# 1-Schematic_Mailbox_Sensor_eLab.net
KiCad netlist of a schematic drawn in EasyEDA
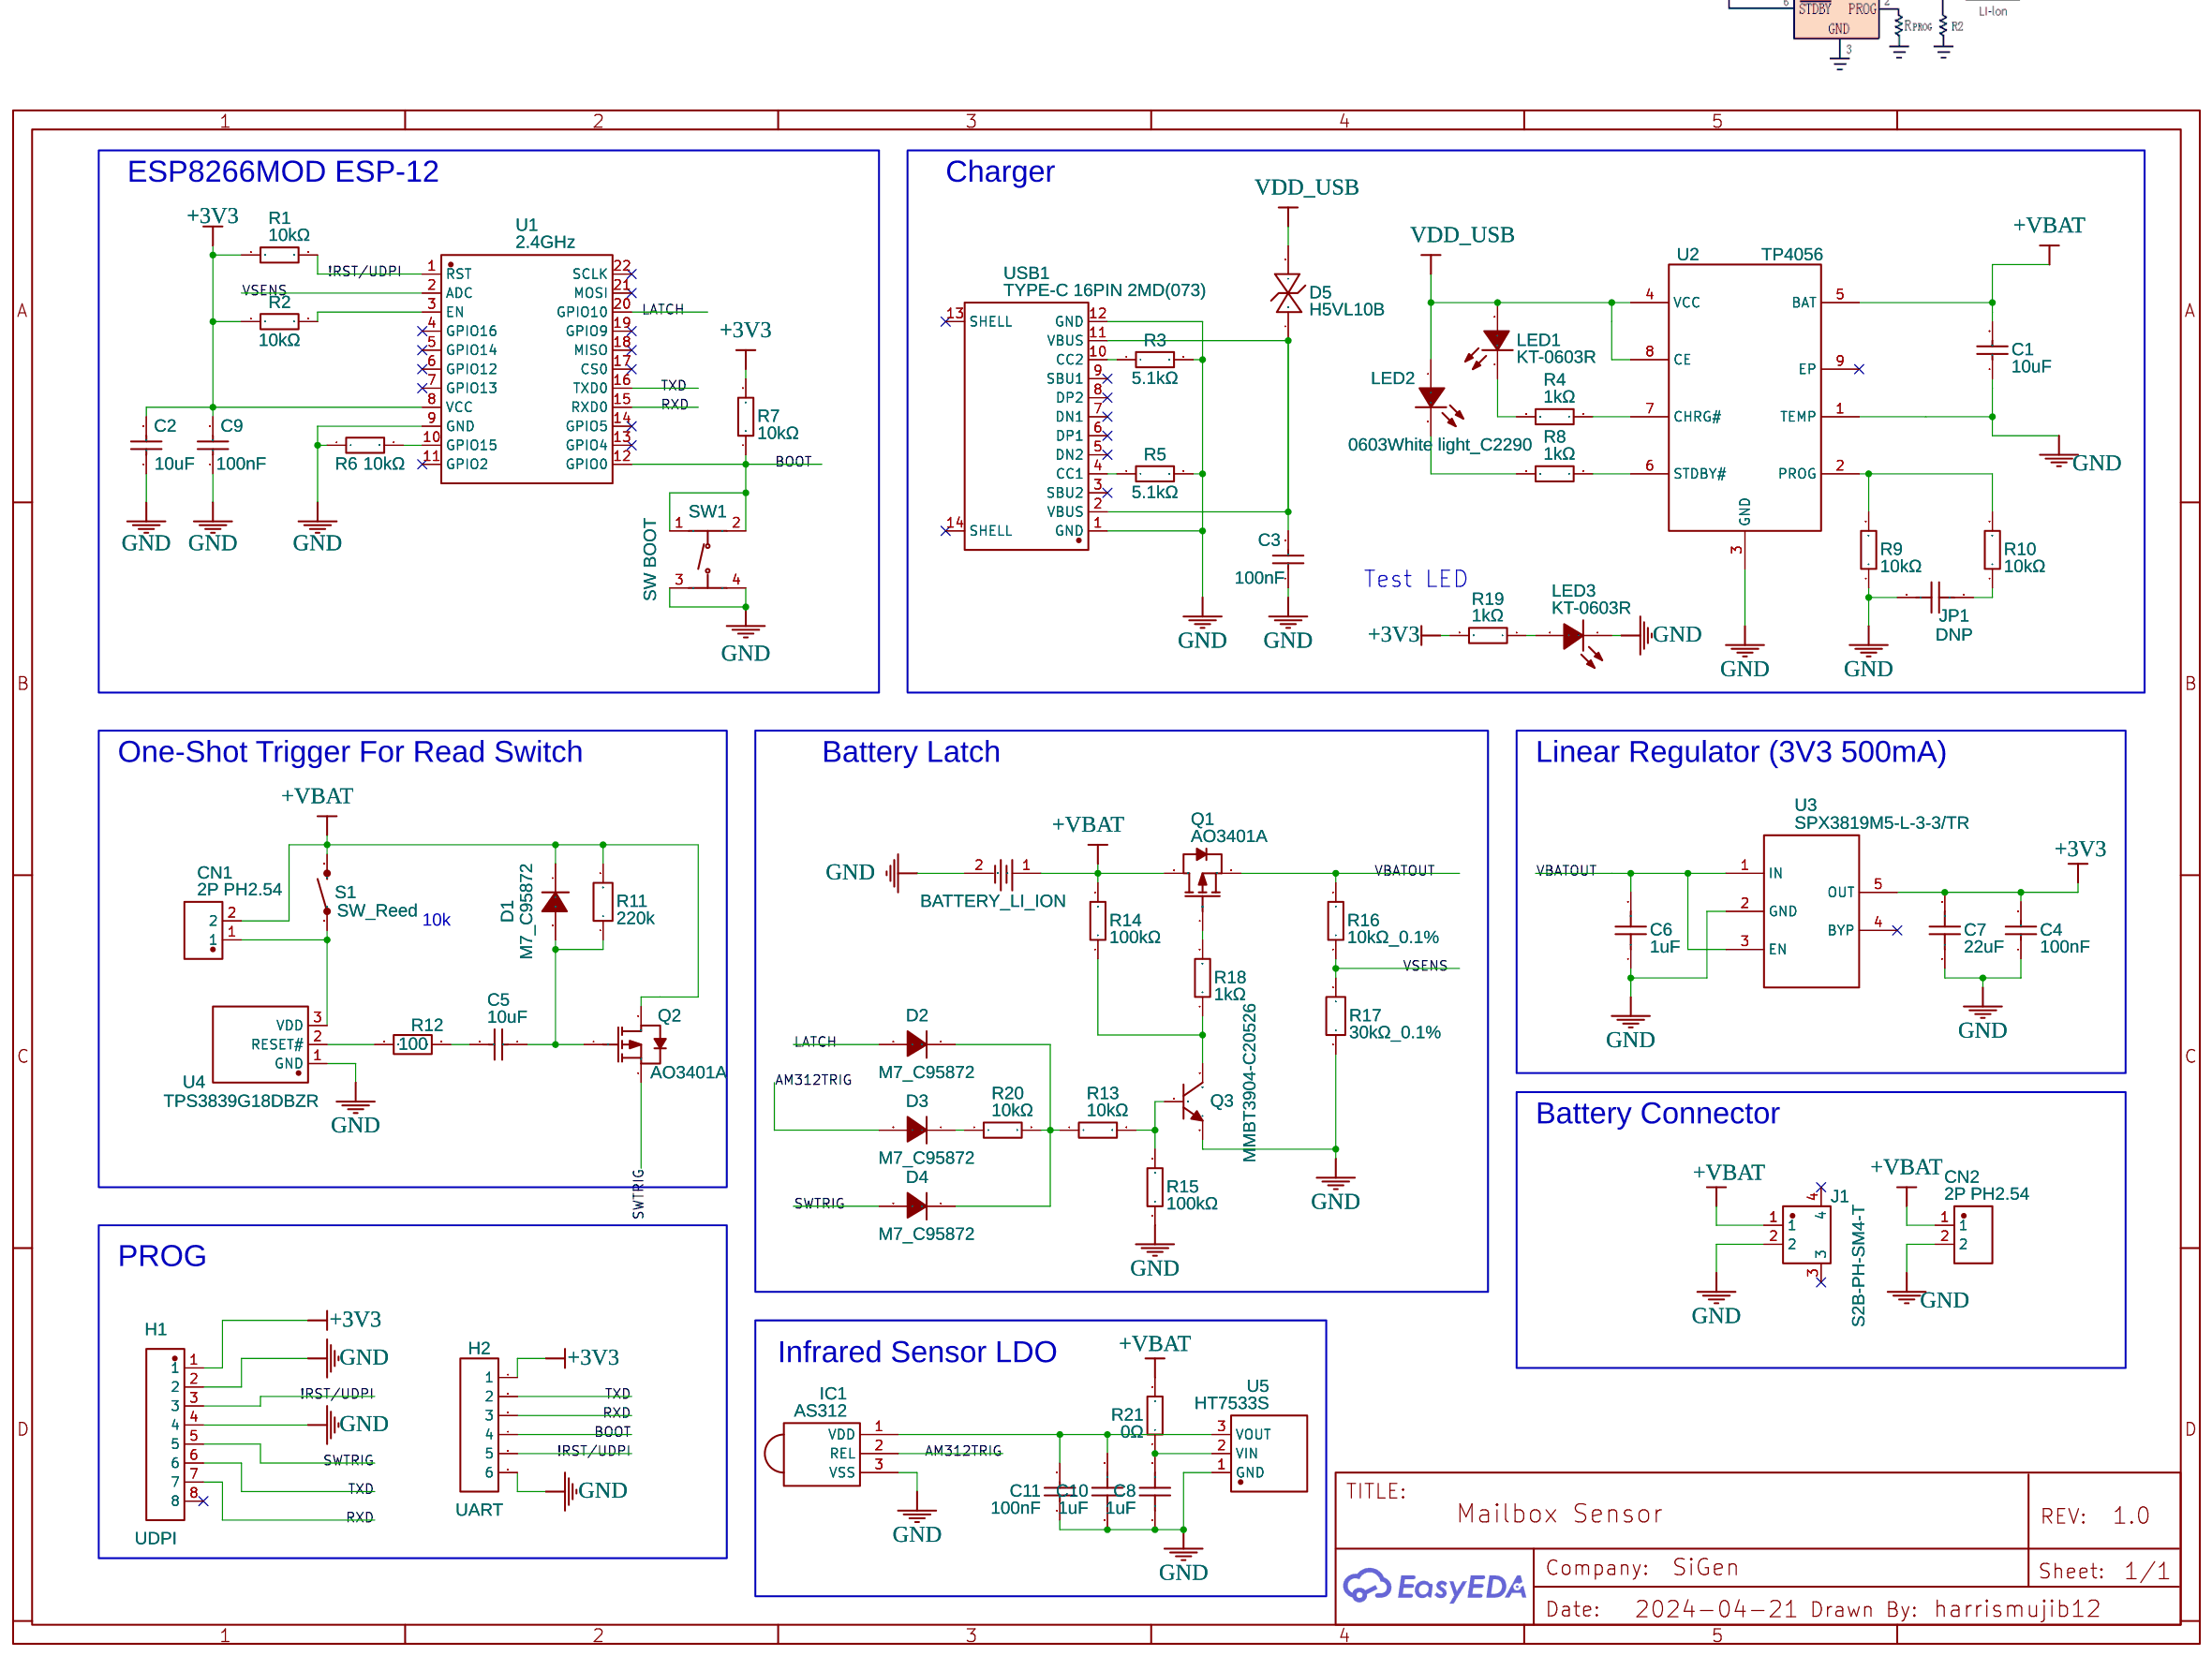
[diagram p0: schematic sheet]

(export (version "E")
  (design (tool "Eeschema 10.0.6"))
  (components
    (comp (ref "BATTERY_LI_ION")
      (value "CR1220-2")
      (fields (field (name "Manufacturer") "Q&J"))
      (libsource (lib "") (part "CR1220-2"))
    )
    (comp (ref "C1")
      (value "10uF")
      (fields
        (field (name "Manufacturer Part") "CL05A106MQ5NUNC")
        (field (name "Manufacturer") "SAMSUNG(三星)")
      )
      (libsource (lib "") (part "CL05A106MQ5NUNC"))
    )
    (comp (ref "C2")
      (value "10uF")
      (fields
        (field (name "Manufacturer Part") "CL05A106MQ5NUNC")
        (field (name "Manufacturer") "SAMSUNG(三星)")
      )
      (libsource (lib "") (part "CL05A106MQ5NUNC"))
    )
    (comp (ref "C3")
      (value "100nF")
      (fields
        (field (name "Manufacturer Part") "CL05B104KO5NNNC")
        (field (name "Manufacturer") "SAMSUNG(三星)")
      )
      (libsource (lib "") (part "CL05B104KO5NNNC"))
    )
    (comp (ref "C4")
      (value "100nF")
      (fields
        (field (name "Manufacturer Part") "CL05B104KO5NNNC")
        (field (name "Manufacturer") "SAMSUNG(三星)")
      )
      (libsource (lib "") (part "CL05B104KO5NNNC"))
    )
    (comp (ref "C5")
      (value "10uF")
      (fields
        (field (name "Manufacturer Part") "CL05A106MQ5NUNC")
        (field (name "Manufacturer") "SAMSUNG(三星)")
      )
      (libsource (lib "") (part "CL05A106MQ5NUNC_1"))
    )
    (comp (ref "C6")
      (value "1uF")
      (fields
        (field (name "Manufacturer Part") "CL05A105KA5NQNC")
        (field (name "Manufacturer") "SAMSUNG(三星)")
      )
      (libsource (lib "") (part "CL05A105KA5NQNC_1"))
    )
    (comp (ref "C7")
      (value "22uF")
      (fields
        (field (name "Manufacturer Part") "CL10A226MQ8NRNC")
        (field (name "Manufacturer") "SAMSUNG(三星)")
      )
      (libsource (lib "") (part "CL10A226MQ8NRNC"))
    )
    (comp (ref "C8")
      (value "1uF")
      (fields
        (field (name "Manufacturer Part") "CL05A105KA5NQNC")
        (field (name "Manufacturer") "SAMSUNG(三星)")
      )
      (libsource (lib "") (part "CL05A105KA5NQNC"))
    )
    (comp (ref "C9")
      (value "100nF")
      (fields
        (field (name "Manufacturer Part") "CL05B104KO5NNNC")
        (field (name "Manufacturer") "SAMSUNG(三星)")
      )
      (libsource (lib "") (part "CL05B104KO5NNNC"))
    )
    (comp (ref "C10")
      (value "1uF")
      (fields
        (field (name "Manufacturer Part") "CL05A105KA5NQNC")
        (field (name "Manufacturer") "SAMSUNG(三星)")
      )
      (libsource (lib "") (part "CL05A105KA5NQNC"))
    )
    (comp (ref "C11")
      (value "100nF")
      (fields
        (field (name "Manufacturer Part") "CL05B104KO5NNNC")
        (field (name "Manufacturer") "SAMSUNG(三星)")
      )
      (libsource (lib "") (part "CL05B104KO5NNNC_1"))
    )
    (comp (ref "CN1") (value "2P PH2.54") (libsource (lib "") (part "2P PH2.54_1")))
    (comp (ref "CN2") (value "2P PH2.54") (libsource (lib "") (part "2P PH2.54")))
    (comp (ref "D1")
      (value "M7_C95872")
      (fields (field (name "Manufacturer Part") "M7") (field (name "Manufacturer") "MDD"))
      (libsource (lib "") (part "M7_C95872_1"))
    )
    (comp (ref "D2")
      (value "M7_C95872")
      (fields (field (name "Manufacturer Part") "M7") (field (name "Manufacturer") "MDD"))
      (libsource (lib "") (part "M7_C95872"))
    )
    (comp (ref "D3")
      (value "M7_C95872")
      (fields (field (name "Manufacturer Part") "M7") (field (name "Manufacturer") "MDD"))
      (libsource (lib "") (part "M7_C95872"))
    )
    (comp (ref "D4")
      (value "M7_C95872")
      (fields (field (name "Manufacturer Part") "M7") (field (name "Manufacturer") "MDD"))
      (libsource (lib "") (part "M7_C95872"))
    )
    (comp (ref "D5")
      (value "H5VL10B")
      (fields (field (name "Manufacturer") "宏迦橙"))
      (libsource (lib "") (part "H5VL10B"))
    )
    (comp (ref "H1")
      (value "UDPI")
      (fields (field (name "Manufacturer Part") "PZ254V-11-08P") (field (name "Manufacturer") "XFCN(兴飞)"))
      (libsource (lib "") (part "PZ254V-11-08P"))
    )
    (comp (ref "H2")
      (value "UART")
      (fields (field (name "Manufacturer Part") "2.54-1x6P直针") (field (name "Manufacturer") "BOOMELE(博穆精密)"))
      (libsource (lib "") (part "Header-Male-2.54_1x6"))
    )
    (comp (ref "IC1")
      (value "AS312")
      (fields (field (name "Manufacturer") "森霸"))
      (libsource (lib "") (part "AS312"))
    )
    (comp (ref "J1")
      (value "S2B-PH-SM4-T")
      (fields (field (name "Manufacturer") "JST"))
      (libsource (lib "") (part "S2B-PH-SM4-TB(LF)(SN)"))
    )
    (comp (ref "JP1")
      (value "DNP")
      (fields
        (field (name "Manufacturer Part") "CQ0402ARNPO0BN1R0")
        (field (name "Manufacturer") "YAGEO(国巨)")
      )
      (libsource (lib "") (part "CQ0402ARNPO0BN1R0"))
    )
    (comp (ref "LED1")
      (value "KT-0603R")
      (fields (field (name "Manufacturer") "KENTO"))
      (libsource (lib "") (part "KT-0603R"))
    )
    (comp (ref "LED2")
      (value "0603White light_C2290")
      (fields (field (name "Manufacturer Part") "KT-0603白灯") (field (name "Manufacturer") "KENTO"))
      (libsource (lib "") (part "0603White light_C2290"))
    )
    (comp (ref "LED3")
      (value "KT-0603R")
      (fields (field (name "Manufacturer") "KENTO"))
      (libsource (lib "") (part "KT-0603R_1"))
    )
    (comp (ref "Q1")
      (value "AO3401A")
      (fields (field (name "Manufacturer") "AOS"))
      (libsource (lib "") (part "AO3401A_1"))
    )
    (comp (ref "Q2")
      (value "AO3401A")
      (fields (field (name "Manufacturer") "AOS"))
      (libsource (lib "") (part "AO3401A"))
    )
    (comp (ref "Q3")
      (value "MMBT3904-C20526")
      (fields (field (name "Manufacturer Part") "MMBT3904") (field (name "Manufacturer") "CJ"))
      (libsource (lib "") (part "MMBT3904-C20526"))
    )
    (comp (ref "R1")
      (value "10kΩ")
      (fields
        (field (name "Manufacturer Part") "0402WGF1002TCE")
        (field (name "Manufacturer") "UNI-ROYAL(厚声)")
      )
      (libsource (lib "") (part "0402WGF1002TCE_1"))
    )
    (comp (ref "R2")
      (value "10kΩ")
      (fields
        (field (name "Manufacturer Part") "0402WGF1002TCE")
        (field (name "Manufacturer") "UNI-ROYAL(厚声)")
      )
      (libsource (lib "") (part "0402WGF1002TCE_1"))
    )
    (comp (ref "R3")
      (value "5.1kΩ")
      (fields
        (field (name "Manufacturer Part") "0402WGF5101TCE")
        (field (name "Manufacturer") "UNI-ROYAL(厚声)")
      )
      (libsource (lib "") (part "0402WGF5101TCE"))
    )
    (comp (ref "R4")
      (value "1kΩ")
      (fields
        (field (name "Manufacturer Part") "0402WGF1001TCE")
        (field (name "Manufacturer") "UNI-ROYAL(厚声)")
      )
      (libsource (lib "") (part "0402WGF1001TCE"))
    )
    (comp (ref "R5")
      (value "5.1kΩ")
      (fields
        (field (name "Manufacturer Part") "0402WGF5101TCE")
        (field (name "Manufacturer") "UNI-ROYAL(厚声)")
      )
      (libsource (lib "") (part "0402WGF5101TCE"))
    )
    (comp (ref "R6")
      (value "10kΩ")
      (fields
        (field (name "Manufacturer Part") "0402WGF1002TCE")
        (field (name "Manufacturer") "UNI-ROYAL(厚声)")
      )
      (libsource (lib "") (part "0402WGF1002TCE_1"))
    )
    (comp (ref "R7")
      (value "10kΩ")
      (fields
        (field (name "Manufacturer Part") "0402WGF1002TCE")
        (field (name "Manufacturer") "UNI-ROYAL(厚声)")
      )
      (libsource (lib "") (part "0402WGF1002TCE"))
    )
    (comp (ref "R8")
      (value "1kΩ")
      (fields
        (field (name "Manufacturer Part") "0402WGF1001TCE")
        (field (name "Manufacturer") "UNI-ROYAL(厚声)")
      )
      (libsource (lib "") (part "0402WGF1001TCE"))
    )
    (comp (ref "R9")
      (value "10kΩ")
      (fields
        (field (name "Manufacturer Part") "0402WGF1002TCE")
        (field (name "Manufacturer") "UNI-ROYAL(厚声)")
      )
      (libsource (lib "") (part "0402WGF1002TCE"))
    )
    (comp (ref "R10")
      (value "10kΩ")
      (fields
        (field (name "Manufacturer Part") "0402WGF1002TCE")
        (field (name "Manufacturer") "UNI-ROYAL(厚声)")
      )
      (libsource (lib "") (part "0402WGF1002TCE"))
    )
    (comp (ref "R11") (value "220k") (libsource (lib "") (part "R_0603_EU_1")))
    (comp (ref "R12") (value "100") (libsource (lib "") (part "R_0603_EU")))
    (comp (ref "R13")
      (value "10kΩ")
      (fields
        (field (name "Manufacturer Part") "0402WGF1002TCE")
        (field (name "Manufacturer") "UNI-ROYAL(厚声)")
      )
      (libsource (lib "") (part "0402WGF1002TCE_1"))
    )
    (comp (ref "R14")
      (value "100kΩ")
      (fields
        (field (name "Manufacturer Part") "0603WAF1003T5E")
        (field (name "Manufacturer") "UNI-ROYAL(厚声)")
      )
      (libsource (lib "") (part "0603WAF1003T5E"))
    )
    (comp (ref "R15")
      (value "100kΩ")
      (fields
        (field (name "Manufacturer Part") "0603WAF1003T5E")
        (field (name "Manufacturer") "UNI-ROYAL(厚声)")
      )
      (libsource (lib "") (part "0603WAF1003T5E"))
    )
    (comp (ref "R16")
      (value "10kΩ_0.1%")
      (fields (field (name "Manufacturer Part") "RT0402BRD0710KL") (field (name "Manufacturer") "YAGEO(国巨)"))
      (libsource (lib "") (part "RT0402BRD0710KL"))
    )
    (comp (ref "R17")
      (value "30kΩ_0.1%")
      (fields (field (name "Manufacturer Part") "RT0402BRD0730KL") (field (name "Manufacturer") "YAGEO(国巨)"))
      (libsource (lib "") (part "RT0402BRD0730KL"))
    )
    (comp (ref "R18")
      (value "1kΩ")
      (fields
        (field (name "Manufacturer Part") "0402WGF1001TCE")
        (field (name "Manufacturer") "UNI-ROYAL(厚声)")
      )
      (libsource (lib "") (part "0402WGF1001TCE_1"))
    )
    (comp (ref "R19")
      (value "1kΩ")
      (fields
        (field (name "Manufacturer Part") "0402WGF1001TCE")
        (field (name "Manufacturer") "UNI-ROYAL(厚声)")
      )
      (libsource (lib "") (part "0402WGF1001TCE"))
    )
    (comp (ref "R20")
      (value "10kΩ")
      (fields
        (field (name "Manufacturer Part") "0402WGF1002TCE")
        (field (name "Manufacturer") "UNI-ROYAL(厚声)")
      )
      (libsource (lib "") (part "0402WGF1002TCE_1"))
    )
    (comp (ref "R21")
      (value "0Ω")
      (fields
        (field (name "Manufacturer Part") "0402WGJ0000TCE")
        (field (name "Manufacturer") "UNI-ROYAL(厚声)")
      )
      (libsource (lib "") (part "0402WGJ0000TCE"))
    )
    (comp (ref "S1") (value "SW_Reed") (libsource (lib "") (part "SWITCH-MOMENTARYPTH_REED")))
    (comp (ref "SW1")
      (value "SW BOOT")
      (fields
        (field (name "Manufacturer Part") "TS-1187A-B-A-B")
        (field (name "Manufacturer") "XKB Connectivity(中国星坤)")
      )
      (libsource (lib "") (part "TS-1187A-B-A-B"))
    )
    (comp (ref "U1")
      (value "2.4GHz")
      (fields
        (field (name "Manufacturer Part") "ESP-12F(ESP8266MOD)")
        (field (name "Manufacturer") "Ai-Thinker(安信可)")
      )
      (libsource (lib "") (part "ESP-12F(ESP8266MOD)"))
    )
    (comp (ref "U2")
      (value "TP4056")
      (fields
        (field (name "Manufacturer Part") "TP4056-42-ESOP8")
        (field (name "Manufacturer") "TOPPOWER(南京拓微)")
      )
      (libsource (lib "") (part "TP4056"))
    )
    (comp (ref "U3")
      (value "SPX3819M5-L-3-3/TR")
      (fields (field (name "Manufacturer") "MaxLinear"))
      (libsource (lib "") (part "SPX3819M5-L-3-3/TR"))
    )
    (comp (ref "U4")
      (value "TPS3839G18DBZR")
      (fields (field (name "Manufacturer") "TI(德州仪器)"))
      (libsource (lib "") (part "TPS3839G18DBZR"))
    )
    (comp (ref "U5")
      (value "HT7533S")
      (fields (field (name "Manufacturer") "UMW(友台半导体)"))
      (libsource (lib "") (part "HT7533S"))
    )
    (comp (ref "USB1")
      (value "TYPE-C 16PIN 2MD(073)")
      (fields (field (name "Manufacturer") "SHOU HAN(首韩)"))
      (libsource (lib "") (part "TYPE-C 16PIN 2MD(073)"))
    )
  )
  (nets
    (net (code "1") (name "+3V3") (class "Default")
      (node (ref "C2") (pin "2") (pinfunction "2_2") (pintype "input"))
      (node (ref "C4") (pin "2") (pinfunction "2_2") (pintype "input"))
      (node (ref "C7") (pin "2") (pinfunction "2_2") (pintype "unspecified"))
      (node (ref "C9") (pin "2") (pinfunction "2_2") (pintype "input"))
      (node (ref "H1") (pin "1") (pinfunction "1_1") (pintype "unspecified"))
      (node (ref "H2") (pin "1") (pinfunction "1_1") (pintype "input"))
      (node (ref "R1") (pin "1") (pinfunction "1_1") (pintype "input"))
      (node (ref "R19") (pin "2") (pinfunction "2_2") (pintype "input"))
      (node (ref "R2") (pin "1") (pinfunction "1_1") (pintype "input"))
      (node (ref "R7") (pin "2") (pinfunction "2_2") (pintype "input"))
      (node (ref "U1") (pin "8") (pinfunction "VCC_8") (pintype "unspecified"))
      (node (ref "U3") (pin "5") (pinfunction "OUT_5") (pintype "unspecified"))
    )
    (net (code "2") (name "+VBAT") (class "Default")
      (node (ref "BATTERY_LI_ION") (pin "1") (pinfunction "1_1") (pintype "input"))
      (node (ref "C1") (pin "2") (pinfunction "2_2") (pintype "input"))
      (node (ref "CN1") (pin "2") (pinfunction "2_2") (pintype "unspecified"))
      (node (ref "CN2") (pin "1") (pinfunction "1_1") (pintype "unspecified"))
      (node (ref "D1") (pin "1") (pinfunction "K_1") (pintype "unspecified"))
      (node (ref "J1") (pin "1") (pinfunction "1_1") (pintype "unspecified"))
      (node (ref "Q1") (pin "3") (pinfunction "D_3") (pintype "unspecified"))
      (node (ref "Q2") (pin "3") (pinfunction "D_3") (pintype "unspecified"))
      (node (ref "R11") (pin "2") (pinfunction "2_2") (pintype "unspecified"))
      (node (ref "R14") (pin "2") (pinfunction "2_2") (pintype "input"))
      (node (ref "R21") (pin "2") (pinfunction "2_2") (pintype "input"))
      (node (ref "S1") (pin "P$2") (pinfunction "2_P$2") (pintype "unspecified"))
      (node (ref "U2") (pin "5") (pinfunction "BAT_5") (pintype "unspecified"))
    )
    (net (code "3") (name "/!RST{slash}UDPI") (class "Default")
      (node (ref "H1") (pin "3") (pinfunction "3_3") (pintype "unspecified"))
      (node (ref "H2") (pin "5") (pinfunction "5_5") (pintype "input"))
      (node (ref "R1") (pin "2") (pinfunction "2_2") (pintype "input"))
      (node (ref "U1") (pin "1") (pinfunction "RST_1") (pintype "unspecified"))
    )
    (net (code "4") (name "/AM312TRIG") (class "Default")
      (node (ref "D3") (pin "2") (pinfunction "A_2") (pintype "unspecified"))
      (node (ref "IC1") (pin "2") (pinfunction "REL_2") (pintype "input"))
    )
    (net (code "5") (name "/BOOT") (class "Default")
      (node (ref "H2") (pin "4") (pinfunction "4_4") (pintype "input"))
      (node (ref "R7") (pin "1") (pinfunction "1_1") (pintype "input"))
      (node (ref "SW1") (pin "1") (pinfunction "A_1") (pintype "unspecified"))
      (node (ref "SW1") (pin "2") (pinfunction "B_2") (pintype "unspecified"))
      (node (ref "U1") (pin "12") (pinfunction "GPIO0_12") (pintype "unspecified"))
    )
    (net (code "6") (name "/LATCH") (class "Default")
      (node (ref "D2") (pin "2") (pinfunction "A_2") (pintype "unspecified"))
      (node (ref "U1") (pin "20") (pinfunction "GPIO10_20") (pintype "unspecified"))
    )
    (net (code "7") (name "/RXD") (class "Default")
      (node (ref "H1") (pin "7") (pinfunction "7_7") (pintype "unspecified"))
      (node (ref "H2") (pin "3") (pinfunction "3_3") (pintype "input"))
      (node (ref "U1") (pin "15") (pinfunction "RXD0_15") (pintype "unspecified"))
    )
    (net (code "8") (name "/SWTRIG") (class "Default")
      (node (ref "D4") (pin "2") (pinfunction "A_2") (pintype "unspecified"))
      (node (ref "H1") (pin "5") (pinfunction "5_5") (pintype "unspecified"))
      (node (ref "Q2") (pin "2") (pinfunction "S_2") (pintype "unspecified"))
    )
    (net (code "9") (name "/TXD") (class "Default")
      (node (ref "H1") (pin "6") (pinfunction "6_6") (pintype "unspecified"))
      (node (ref "H2") (pin "2") (pinfunction "2_2") (pintype "input"))
      (node (ref "U1") (pin "16") (pinfunction "TXD0_16") (pintype "unspecified"))
    )
    (net (code "10") (name "/VBATOUT") (class "Default")
      (node (ref "C6") (pin "2") (pinfunction "2_2") (pintype "unspecified"))
      (node (ref "Q1") (pin "2") (pinfunction "S_2") (pintype "unspecified"))
      (node (ref "R16") (pin "2") (pinfunction "2_2") (pintype "unspecified"))
      (node (ref "U3") (pin "1") (pinfunction "IN_1") (pintype "unspecified"))
      (node (ref "U3") (pin "3") (pinfunction "EN_3") (pintype "unspecified"))
    )
    (net (code "11") (name "/VSENS") (class "Default")
      (node (ref "R16") (pin "1") (pinfunction "1_1") (pintype "unspecified"))
      (node (ref "R17") (pin "2") (pinfunction "2_2") (pintype "unspecified"))
      (node (ref "U1") (pin "2") (pinfunction "ADC_2") (pintype "unspecified"))
    )
    (net (code "12") (name "GND") (class "Default")
      (node (ref "BATTERY_LI_ION") (pin "2") (pinfunction "2_2") (pintype "input"))
      (node (ref "C1") (pin "1") (pinfunction "1_1") (pintype "input"))
      (node (ref "C10") (pin "1") (pinfunction "1_1") (pintype "unspecified"))
      (node (ref "C11") (pin "1") (pinfunction "1_1") (pintype "input"))
      (node (ref "C2") (pin "1") (pinfunction "1_1") (pintype "input"))
      (node (ref "C3") (pin "1") (pinfunction "1_1") (pintype "input"))
      (node (ref "C4") (pin "1") (pinfunction "1_1") (pintype "input"))
      (node (ref "C6") (pin "1") (pinfunction "1_1") (pintype "unspecified"))
      (node (ref "C7") (pin "1") (pinfunction "1_1") (pintype "unspecified"))
      (node (ref "C8") (pin "1") (pinfunction "1_1") (pintype "unspecified"))
      (node (ref "C9") (pin "1") (pinfunction "1_1") (pintype "input"))
      (node (ref "CN2") (pin "2") (pinfunction "2_2") (pintype "unspecified"))
      (node (ref "H1") (pin "2") (pinfunction "2_2") (pintype "unspecified"))
      (node (ref "H1") (pin "4") (pinfunction "4_4") (pintype "unspecified"))
      (node (ref "H2") (pin "6") (pinfunction "6_6") (pintype "input"))
      (node (ref "IC1") (pin "3") (pinfunction "VSS_3") (pintype "input"))
      (node (ref "J1") (pin "2") (pinfunction "2_2") (pintype "unspecified"))
      (node (ref "JP1") (pin "2") (pinfunction "2_2") (pintype "unspecified"))
      (node (ref "LED3") (pin "1") (pinfunction "K_1") (pintype "unspecified"))
      (node (ref "Q3") (pin "2") (pinfunction "E_2") (pintype "unspecified"))
      (node (ref "R15") (pin "1") (pinfunction "1_1") (pintype "input"))
      (node (ref "R17") (pin "1") (pinfunction "1_1") (pintype "unspecified"))
      (node (ref "R3") (pin "2") (pinfunction "2_2") (pintype "input"))
      (node (ref "R5") (pin "2") (pinfunction "2_2") (pintype "input"))
      (node (ref "R6") (pin "1") (pinfunction "1_1") (pintype "input"))
      (node (ref "R9") (pin "1") (pinfunction "1_1") (pintype "input"))
      (node (ref "SW1") (pin "3") (pinfunction "C_3") (pintype "unspecified"))
      (node (ref "SW1") (pin "4") (pinfunction "D_4") (pintype "unspecified"))
      (node (ref "U1") (pin "9") (pinfunction "GND_9") (pintype "unspecified"))
      (node (ref "U2") (pin "1") (pinfunction "TEMP_1") (pintype "unspecified"))
      (node (ref "U2") (pin "3") (pinfunction "GND_3") (pintype "unspecified"))
      (node (ref "U3") (pin "2") (pinfunction "GND_2") (pintype "unspecified"))
      (node (ref "U4") (pin "1") (pinfunction "GND_1") (pintype "unspecified"))
      (node (ref "U5") (pin "1") (pinfunction "GND_1") (pintype "unspecified"))
      (node (ref "USB1") (pin "1") (pinfunction "GND_1") (pintype "unspecified"))
      (node (ref "USB1") (pin "12") (pinfunction "GND_12") (pintype "unspecified"))
    )
    (net (code "13") (name "Net-(C5-Pad2)") (class "Default")
      (node (ref "C5") (pin "2") (pinfunction "2_2") (pintype "input"))
      (node (ref "R12") (pin "2") (pinfunction "2_2") (pintype "unspecified"))
    )
    (net (code "14") (name "Net-(D1-A)") (class "Default")
      (node (ref "C5") (pin "1") (pinfunction "1_1") (pintype "input"))
      (node (ref "D1") (pin "2") (pinfunction "A_2") (pintype "unspecified"))
      (node (ref "Q2") (pin "1") (pinfunction "G_1") (pintype "unspecified"))
      (node (ref "R11") (pin "1") (pinfunction "1_1") (pintype "unspecified"))
    )
    (net (code "15") (name "Net-(D2-K)") (class "Default")
      (node (ref "D2") (pin "1") (pinfunction "K_1") (pintype "unspecified"))
      (node (ref "D4") (pin "1") (pinfunction "K_1") (pintype "unspecified"))
      (node (ref "R13") (pin "1") (pinfunction "1_1") (pintype "input"))
      (node (ref "R20") (pin "2") (pinfunction "2_2") (pintype "input"))
    )
    (net (code "16") (name "Net-(D3-K)") (class "Default")
      (node (ref "D3") (pin "1") (pinfunction "K_1") (pintype "unspecified"))
      (node (ref "R20") (pin "1") (pinfunction "1_1") (pintype "input"))
    )
    (net (code "17") (name "Net-(D5-C)") (class "Default")
      (node (ref "C3") (pin "2") (pinfunction "2_2") (pintype "input"))
      (node (ref "D5") (pin "1") (pinfunction "C_1") (pintype "unspecified"))
      (node (ref "USB1") (pin "11") (pinfunction "VBUS_11") (pintype "unspecified"))
      (node (ref "USB1") (pin "2") (pinfunction "VBUS_2") (pintype "unspecified"))
    )
    (net (code "18") (name "Net-(IC1-VDD)") (class "Default")
      (node (ref "C10") (pin "2") (pinfunction "2_2") (pintype "unspecified"))
      (node (ref "C11") (pin "2") (pinfunction "2_2") (pintype "input"))
      (node (ref "IC1") (pin "1") (pinfunction "VDD_1") (pintype "input"))
      (node (ref "U5") (pin "3") (pinfunction "VOUT_3") (pintype "unspecified"))
    )
    (net (code "19") (name "Net-(JP1-Pad1)") (class "Default")
      (node (ref "JP1") (pin "1") (pinfunction "1_1") (pintype "unspecified"))
      (node (ref "R10") (pin "1") (pinfunction "1_1") (pintype "input"))
    )
    (net (code "20") (name "Net-(LED1-K)") (class "Default")
      (node (ref "LED1") (pin "1") (pinfunction "K_1") (pintype "unspecified"))
      (node (ref "R4") (pin "2") (pinfunction "2_2") (pintype "input"))
    )
    (net (code "21") (name "Net-(LED2-K)") (class "Default")
      (node (ref "LED2") (pin "2") (pinfunction "K_2") (pintype "unspecified"))
      (node (ref "R8") (pin "2") (pinfunction "2_2") (pintype "input"))
    )
    (net (code "22") (name "Net-(LED3-A)") (class "Default")
      (node (ref "LED3") (pin "2") (pinfunction "A_2") (pintype "unspecified"))
      (node (ref "R19") (pin "1") (pinfunction "1_1") (pintype "input"))
    )
    (net (code "23") (name "Net-(Q1-G)") (class "Default")
      (node (ref "Q1") (pin "1") (pinfunction "G_1") (pintype "unspecified"))
      (node (ref "R18") (pin "2") (pinfunction "2_2") (pintype "input"))
    )
    (net (code "24") (name "Net-(Q3-B)") (class "Default")
      (node (ref "Q3") (pin "1") (pinfunction "B_1") (pintype "unspecified"))
      (node (ref "R13") (pin "2") (pinfunction "2_2") (pintype "input"))
      (node (ref "R15") (pin "2") (pinfunction "2_2") (pintype "input"))
    )
    (net (code "25") (name "Net-(Q3-C)") (class "Default")
      (node (ref "Q3") (pin "3") (pinfunction "C_3") (pintype "unspecified"))
      (node (ref "R14") (pin "1") (pinfunction "1_1") (pintype "input"))
      (node (ref "R18") (pin "1") (pinfunction "1_1") (pintype "input"))
    )
    (net (code "26") (name "Net-(S1-1)") (class "Default")
      (node (ref "CN1") (pin "1") (pinfunction "1_1") (pintype "unspecified"))
      (node (ref "S1") (pin "P$1") (pinfunction "1_P$1") (pintype "unspecified"))
      (node (ref "U4") (pin "3") (pinfunction "VDD_3") (pintype "unspecified"))
    )
    (net (code "27") (name "Net-(U1-EN)") (class "Default")
      (node (ref "R2") (pin "2") (pinfunction "2_2") (pintype "input"))
      (node (ref "U1") (pin "3") (pinfunction "EN_3") (pintype "unspecified"))
    )
    (net (code "28") (name "Net-(U1-GPIO15)") (class "Default")
      (node (ref "R6") (pin "2") (pinfunction "2_2") (pintype "input"))
      (node (ref "U1") (pin "10") (pinfunction "GPIO15_10") (pintype "unspecified"))
    )
    (net (code "29") (name "Net-(U2-CHRG#)") (class "Default")
      (node (ref "R4") (pin "1") (pinfunction "1_1") (pintype "input"))
      (node (ref "U2") (pin "7") (pinfunction "CHRG#_7") (pintype "unspecified"))
    )
    (net (code "30") (name "Net-(U2-PROG)") (class "Default")
      (node (ref "R10") (pin "2") (pinfunction "2_2") (pintype "input"))
      (node (ref "R9") (pin "2") (pinfunction "2_2") (pintype "input"))
      (node (ref "U2") (pin "2") (pinfunction "PROG_2") (pintype "unspecified"))
    )
    (net (code "31") (name "Net-(U2-STDBY#)") (class "Default")
      (node (ref "R8") (pin "1") (pinfunction "1_1") (pintype "input"))
      (node (ref "U2") (pin "6") (pinfunction "STDBY#_6") (pintype "unspecified"))
    )
    (net (code "32") (name "Net-(U4-RESET#)") (class "Default")
      (node (ref "R12") (pin "1") (pinfunction "1_1") (pintype "unspecified"))
      (node (ref "U4") (pin "2") (pinfunction "RESET#_2") (pintype "unspecified"))
    )
    (net (code "33") (name "Net-(U5-VIN)") (class "Default")
      (node (ref "C8") (pin "2") (pinfunction "2_2") (pintype "unspecified"))
      (node (ref "R21") (pin "1") (pinfunction "1_1") (pintype "input"))
      (node (ref "U5") (pin "2") (pinfunction "VIN_2") (pintype "unspecified"))
    )
    (net (code "34") (name "Net-(USB1-CC1)") (class "Default")
      (node (ref "R5") (pin "1") (pinfunction "1_1") (pintype "input"))
      (node (ref "USB1") (pin "4") (pinfunction "CC1_4") (pintype "unspecified"))
    )
    (net (code "35") (name "Net-(USB1-CC2)") (class "Default")
      (node (ref "R3") (pin "1") (pinfunction "1_1") (pintype "input"))
      (node (ref "USB1") (pin "10") (pinfunction "CC2_10") (pintype "unspecified"))
    )
    (net (code "36") (name "VDD_USB") (class "Default")
      (node (ref "D5") (pin "2") (pinfunction "A_2") (pintype "unspecified"))
      (node (ref "LED1") (pin "2") (pinfunction "A_2") (pintype "unspecified"))
      (node (ref "LED2") (pin "1") (pinfunction "A_1") (pintype "unspecified"))
      (node (ref "U2") (pin "4") (pinfunction "VCC_4") (pintype "unspecified"))
      (node (ref "U2") (pin "8") (pinfunction "CE_8") (pintype "unspecified"))
    )
    (net (code "37") (name "unconnected-(H1-Pad8)") (class "Default")
      (node (ref "H1") (pin "8") (pinfunction "8_8") (pintype "unspecified+no_connect"))
    )
    (net (code "38") (name "unconnected-(J1-Pad3)") (class "Default")
      (node (ref "J1") (pin "3") (pinfunction "3_3") (pintype "unspecified+no_connect"))
    )
    (net (code "39") (name "unconnected-(J1-Pad4)") (class "Default")
      (node (ref "J1") (pin "4") (pinfunction "4_4") (pintype "unspecified+no_connect"))
    )
    (net (code "40") (name "unconnected-(U1-CS0-Pad17)") (class "Default")
      (node (ref "U1") (pin "17") (pinfunction "CS0_17") (pintype "unspecified+no_connect"))
    )
    (net (code "41") (name "unconnected-(U1-GPIO2-Pad11)") (class "Default")
      (node (ref "U1") (pin "11") (pinfunction "GPIO2_11") (pintype "unspecified+no_connect"))
    )
    (net (code "42") (name "unconnected-(U1-GPIO4-Pad13)") (class "Default")
      (node (ref "U1") (pin "13") (pinfunction "GPIO4_13") (pintype "unspecified+no_connect"))
    )
    (net (code "43") (name "unconnected-(U1-GPIO5-Pad14)") (class "Default")
      (node (ref "U1") (pin "14") (pinfunction "GPIO5_14") (pintype "unspecified+no_connect"))
    )
    (net (code "44") (name "unconnected-(U1-GPIO9-Pad19)") (class "Default")
      (node (ref "U1") (pin "19") (pinfunction "GPIO9_19") (pintype "unspecified+no_connect"))
    )
    (net (code "45") (name "unconnected-(U1-GPIO12-Pad6)") (class "Default")
      (node (ref "U1") (pin "6") (pinfunction "GPIO12_6") (pintype "unspecified+no_connect"))
    )
    (net (code "46") (name "unconnected-(U1-GPIO13-Pad7)") (class "Default")
      (node (ref "U1") (pin "7") (pinfunction "GPIO13_7") (pintype "unspecified+no_connect"))
    )
    (net (code "47") (name "unconnected-(U1-GPIO14-Pad5)") (class "Default")
      (node (ref "U1") (pin "5") (pinfunction "GPIO14_5") (pintype "unspecified+no_connect"))
    )
    (net (code "48") (name "unconnected-(U1-GPIO16-Pad4)") (class "Default")
      (node (ref "U1") (pin "4") (pinfunction "GPIO16_4") (pintype "unspecified+no_connect"))
    )
    (net (code "49") (name "unconnected-(U1-MISO-Pad18)") (class "Default")
      (node (ref "U1") (pin "18") (pinfunction "MISO_18") (pintype "unspecified+no_connect"))
    )
    (net (code "50") (name "unconnected-(U1-MOSI-Pad21)") (class "Default")
      (node (ref "U1") (pin "21") (pinfunction "MOSI_21") (pintype "unspecified+no_connect"))
    )
    (net (code "51") (name "unconnected-(U1-SCLK-Pad22)") (class "Default")
      (node (ref "U1") (pin "22") (pinfunction "SCLK_22") (pintype "unspecified+no_connect"))
    )
    (net (code "52") (name "unconnected-(U2-EP-Pad9)") (class "Default")
      (node (ref "U2") (pin "9") (pinfunction "EP_9") (pintype "unspecified+no_connect"))
    )
    (net (code "53") (name "unconnected-(U3-BYP-Pad4)") (class "Default")
      (node (ref "U3") (pin "4") (pinfunction "BYP_4") (pintype "unspecified+no_connect"))
    )
    (net (code "54") (name "unconnected-(USB1-DN1-Pad7)") (class "Default")
      (node (ref "USB1") (pin "7") (pinfunction "DN1_7") (pintype "unspecified+no_connect"))
    )
    (net (code "55") (name "unconnected-(USB1-DN2-Pad5)") (class "Default")
      (node (ref "USB1") (pin "5") (pinfunction "DN2_5") (pintype "unspecified+no_connect"))
    )
    (net (code "56") (name "unconnected-(USB1-DP1-Pad6)") (class "Default")
      (node (ref "USB1") (pin "6") (pinfunction "DP1_6") (pintype "unspecified+no_connect"))
    )
    (net (code "57") (name "unconnected-(USB1-DP2-Pad8)") (class "Default")
      (node (ref "USB1") (pin "8") (pinfunction "DP2_8") (pintype "unspecified+no_connect"))
    )
    (net (code "58") (name "unconnected-(USB1-SBU1-Pad9)") (class "Default")
      (node (ref "USB1") (pin "9") (pinfunction "SBU1_9") (pintype "unspecified+no_connect"))
    )
    (net (code "59") (name "unconnected-(USB1-SBU2-Pad3)") (class "Default")
      (node (ref "USB1") (pin "3") (pinfunction "SBU2_3") (pintype "unspecified+no_connect"))
    )
    (net (code "60") (name "unconnected-(USB1-SHELL-Pad13)") (class "Default")
      (node (ref "USB1") (pin "13") (pinfunction "SHELL_13") (pintype "unspecified+no_connect"))
    )
    (net (code "61") (name "unconnected-(USB1-SHELL-Pad14)") (class "Default")
      (node (ref "USB1") (pin "14") (pinfunction "SHELL_14") (pintype "unspecified+no_connect"))
    )
  )
)
